# X14-Conversion.net
KiCad netlist of a schematic drawn in EAGLE
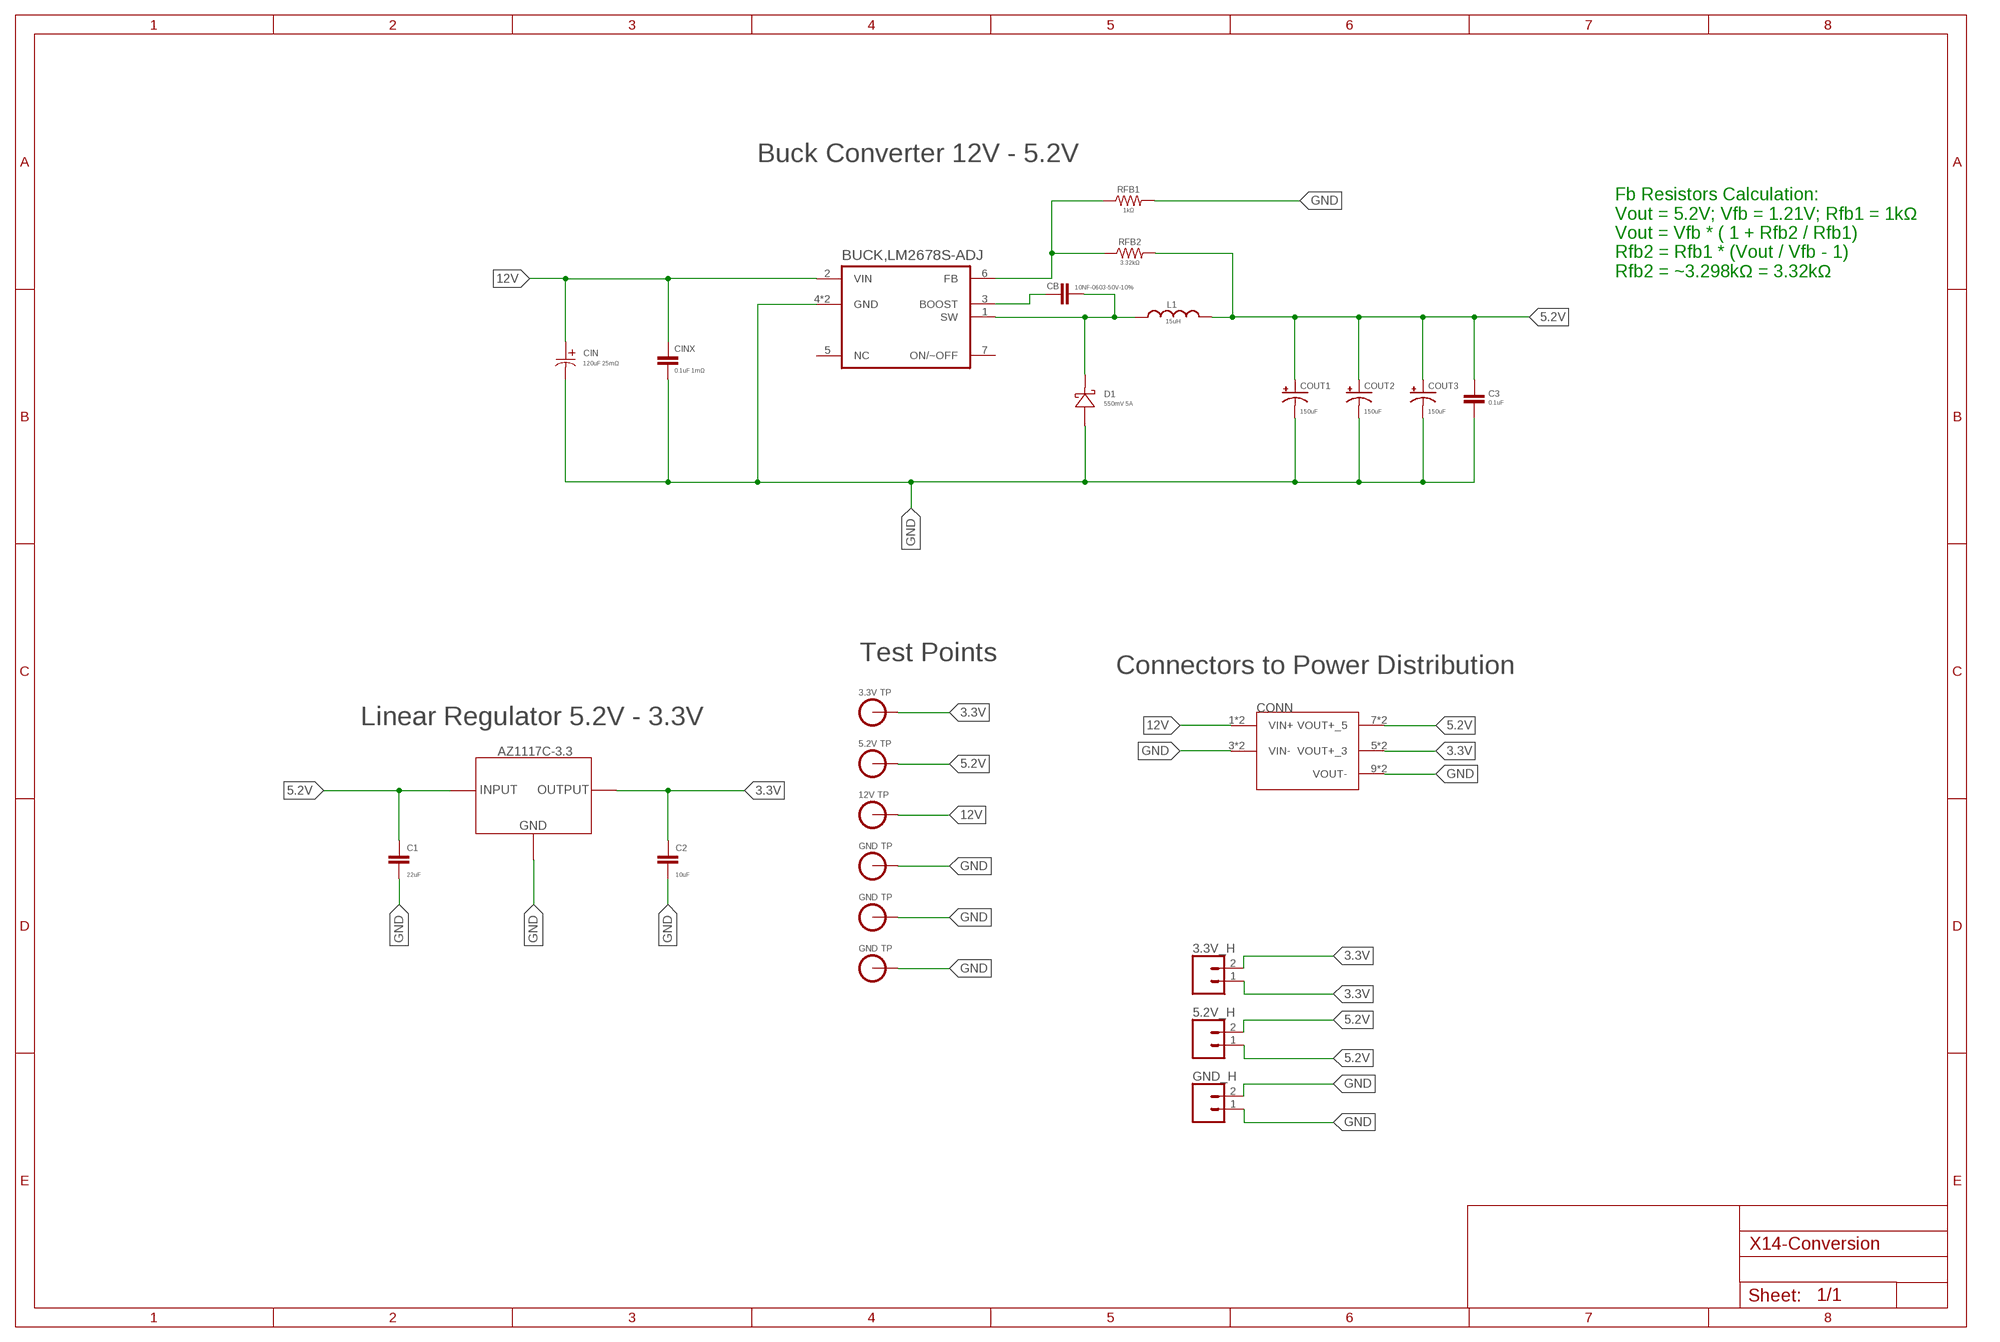
[diagram p0: schematic, sheet 1]

(export (version "E")
  (design (tool "Eeschema 10.0.6"))
  (components
    (comp (ref "3.3V_H")
      (value "CONN_02")
      (footprint "eagle-import:1X02")
      (libsource (lib "eagle-import") (part "CONN_02"))
    )
    (comp (ref "5.2V_H")
      (value "CONN_02")
      (footprint "eagle-import:1X02")
      (libsource (lib "eagle-import") (part "CONN_02"))
    )
    (comp (ref "AZ1117C")
      (value "AZ1117C-3.3")
      (footprint "eagle-import:SOT150P410X160-3N")
      (libsource (lib "eagle-import") (part "SOT150P410X160-3N"))
    )
    (comp (ref "C1")
      (value "22uF")
      (footprint "eagle-import:0805")
      (libsource (lib "eagle-import") (part "22UF-0805-6.3V-20%"))
    )
    (comp (ref "C2")
      (value "10uF")
      (footprint "eagle-import:0603")
      (libsource (lib "eagle-import") (part "10UF-0603-6.3V-20%"))
    )
    (comp (ref "C3")
      (value "0.1uF")
      (footprint "eagle-import:0603")
      (libsource (lib "eagle-import") (part "0.1UF-0603-25V-(+80/-20%)"))
    )
    (comp (ref "CB")
      (value "10NF-0603-50V-10%")
      (footprint "eagle-import:0603")
      (libsource (lib "eagle-import") (part "10NF-0603-50V-10%"))
    )
    (comp (ref "CIN")
      (value "120uF 25mΩ")
      (footprint "eagle-import:PCAP_SVP_C6_PAN")
      (libsource (lib "eagle-import") (part "20SVPF120M"))
    )
    (comp (ref "CINX")
      (value "0.1uF 1mΩ")
      (footprint "eagle-import:0603")
      (libsource (lib "eagle-import") (part "0.1UF-0603-25V-(+80/-20%)"))
    )
    (comp (ref "CONN")
      (value "CONVERSION-DISTRIBUTION")
      (footprint "eagle-import:TSW-105-05-G-S(C-D)")
      (libsource (lib "eagle-import") (part "CONVERSION-DISTRIBUTION"))
    )
    (comp (ref "COUT1")
      (value "150uF")
      (footprint "eagle-import:2917(7343-31-METRIC)")
      (libsource (lib "eagle-import") (part "C-TANTALUM(10UF_150UF)"))
    )
    (comp (ref "COUT2")
      (value "150uF")
      (footprint "eagle-import:2917(7343-31-METRIC)")
      (libsource (lib "eagle-import") (part "C-TANTALUM(10UF_150UF)"))
    )
    (comp (ref "COUT3")
      (value "150uF")
      (footprint "eagle-import:2917(7343-31-METRIC)")
      (libsource (lib "eagle-import") (part "C-TANTALUM(10UF_150UF)"))
    )
    (comp (ref "D1")
      (value "550mV 5A")
      (footprint "eagle-import:CDBG520-G")
      (libsource (lib "eagle-import") (part "CDBG520-G"))
    )
    (comp (ref "GND_H")
      (value "CONN_02")
      (footprint "eagle-import:1X02")
      (libsource (lib "eagle-import") (part "CONN_02"))
    )
    (comp (ref "L1")
      (value "15uH")
      (footprint "eagle-import:HCMA1305")
      (libsource (lib "eagle-import") (part "HCMA1305"))
    )
    (comp (ref "RFB1")
      (value "1kΩ")
      (footprint "eagle-import:0603")
      (libsource (lib "eagle-import") (part "1KOHM-0603-1/10W-1%"))
    )
    (comp (ref "RFB2")
      (value "3.32kΩ")
      (footprint "eagle-import:0603")
      (libsource (lib "eagle-import") (part "3.3KOHM-0603-1/10W-1%"))
    )
    (comp (ref "U$2")
      (value "3.3V_TESTPOINT")
      (footprint "eagle-import:3.3V_TESTPOINT")
      (libsource (lib "eagle-import") (part "3.3V_TESTPOINT"))
    )
    (comp (ref "U$3")
      (value "5.2V_TESTPOINT")
      (footprint "eagle-import:5.2V_TESTPOINT")
      (libsource (lib "eagle-import") (part "5.2V_TESTPOINT"))
    )
    (comp (ref "U$4")
      (value "12V_TESTPOINT")
      (footprint "eagle-import:12V_TESTPOINT")
      (libsource (lib "eagle-import") (part "12V_TESTPOINT"))
    )
    (comp (ref "U$5")
      (value "GND_TESTPOINT")
      (footprint "eagle-import:GND_TESTPOINT")
      (libsource (lib "eagle-import") (part "GND_TESTPOINT"))
    )
    (comp (ref "U$6")
      (value "GND_TESTPOINT")
      (footprint "eagle-import:GND_TESTPOINT")
      (libsource (lib "eagle-import") (part "GND_TESTPOINT"))
    )
    (comp (ref "U$7")
      (value "GND_TESTPOINT")
      (footprint "eagle-import:GND_TESTPOINT")
      (libsource (lib "eagle-import") (part "GND_TESTPOINT"))
    )
    (comp (ref "U1")
      (value "BUCK,LM2678S-ADJ")
      (footprint "eagle-import:TO127P1435X464-8N")
      (fields
        (field (name "DIGI-KEY_PART_NUMBER") "2156-LM2678S-ADJ/NOPB-TI-ND")
        (field (name "MF") "Texas Instruments")
        (field (name "MP") "LM2678S-ADJ")
      )
      (libsource (lib "eagle-import") (part "BUCK,LM2678S-ADJ"))
    )
  )
  (nets
    (net (code "1") (name "3.3V") (class "Default")
      (node (ref "3.3V_H") (pin "1") (pinfunction "1_1") (pintype "passive"))
      (node (ref "3.3V_H") (pin "2") (pinfunction "2_2") (pintype "passive"))
      (node (ref "AZ1117C") (pin "2") (pinfunction "OUTPUT_2") (pintype "bidirectional"))
      (node (ref "AZ1117C") (pin "4") (pinfunction "OUTPUT_4") (pintype "bidirectional"))
      (node (ref "C2") (pin "1") (pinfunction "1_1") (pintype "passive"))
      (node (ref "CONN") (pin "5") (pinfunction "VOUT+_3_5") (pintype "bidirectional"))
      (node (ref "CONN") (pin "6") (pinfunction "VOUT+_3_6") (pintype "bidirectional"))
      (node (ref "U$2") (pin "3.3V") (pinfunction "3.3V_3.3V") (pintype "bidirectional"))
    )
    (net (code "2") (name "5.2V") (class "Default")
      (node (ref "5.2V_H") (pin "1") (pinfunction "1_1") (pintype "passive"))
      (node (ref "5.2V_H") (pin "2") (pinfunction "2_2") (pintype "passive"))
      (node (ref "AZ1117C") (pin "3") (pinfunction "INPUT_3") (pintype "bidirectional"))
      (node (ref "C1") (pin "1") (pinfunction "1_1") (pintype "passive"))
      (node (ref "C3") (pin "1") (pinfunction "1_1") (pintype "passive"))
      (node (ref "CONN") (pin "7") (pinfunction "VOUT+_5_7") (pintype "bidirectional"))
      (node (ref "CONN") (pin "8") (pinfunction "VOUT+_5_8") (pintype "bidirectional"))
      (node (ref "COUT1") (pin "+") (pinfunction "+_+") (pintype "passive"))
      (node (ref "COUT2") (pin "+") (pinfunction "+_+") (pintype "passive"))
      (node (ref "COUT3") (pin "+") (pinfunction "+_+") (pintype "passive"))
      (node (ref "L1") (pin "2") (pinfunction "2_2") (pintype "passive"))
      (node (ref "RFB2") (pin "2") (pinfunction "2_2") (pintype "passive"))
      (node (ref "U$3") (pin "5.2V") (pinfunction "5.2V_5.2V") (pintype "bidirectional"))
    )
    (net (code "3") (name "12V") (class "Default")
      (node (ref "CIN") (pin "1") (pinfunction "1_1") (pintype "passive"))
      (node (ref "CINX") (pin "1") (pinfunction "1_1") (pintype "passive"))
      (node (ref "CONN") (pin "1") (pinfunction "VIN+_1") (pintype "bidirectional"))
      (node (ref "CONN") (pin "2") (pinfunction "VIN+_2") (pintype "bidirectional"))
      (node (ref "U$4") (pin "12V") (pinfunction "12V_12V") (pintype "bidirectional"))
      (node (ref "U1") (pin "2") (pinfunction "VIN_2") (pintype "input"))
    )
    (net (code "4") (name "GND") (class "Default")
      (node (ref "AZ1117C") (pin "1") (pinfunction "GND_1") (pintype "bidirectional"))
      (node (ref "C1") (pin "2") (pinfunction "2_2") (pintype "passive"))
      (node (ref "C2") (pin "2") (pinfunction "2_2") (pintype "passive"))
      (node (ref "C3") (pin "2") (pinfunction "2_2") (pintype "passive"))
      (node (ref "CIN") (pin "2") (pinfunction "2_2") (pintype "passive"))
      (node (ref "CINX") (pin "2") (pinfunction "2_2") (pintype "passive"))
      (node (ref "CONN") (pin "10") (pinfunction "VOUT-_10") (pintype "bidirectional"))
      (node (ref "CONN") (pin "3") (pinfunction "VIN-_3") (pintype "bidirectional"))
      (node (ref "CONN") (pin "4") (pinfunction "VIN-_4") (pintype "bidirectional"))
      (node (ref "CONN") (pin "9") (pinfunction "VOUT-_9") (pintype "bidirectional"))
      (node (ref "COUT1") (pin "-") (pinfunction "-_-") (pintype "passive"))
      (node (ref "COUT2") (pin "-") (pinfunction "-_-") (pintype "passive"))
      (node (ref "COUT3") (pin "-") (pinfunction "-_-") (pintype "passive"))
      (node (ref "D1") (pin "2") (pinfunction "2_2") (pintype "passive"))
      (node (ref "GND_H") (pin "1") (pinfunction "1_1") (pintype "passive"))
      (node (ref "GND_H") (pin "2") (pinfunction "2_2") (pintype "passive"))
      (node (ref "RFB1") (pin "2") (pinfunction "2_2") (pintype "passive"))
      (node (ref "U$5") (pin "GND") (pinfunction "GND_GND") (pintype "bidirectional"))
      (node (ref "U$6") (pin "GND") (pinfunction "GND_GND") (pintype "bidirectional"))
      (node (ref "U$7") (pin "GND") (pinfunction "GND_GND") (pintype "bidirectional"))
      (node (ref "U1") (pin "4") (pinfunction "GND_4") (pintype "power_in"))
      (node (ref "U1") (pin "8") (pinfunction "GND_8") (pintype "power_in"))
    )
    (net (code "5") (name "Net-(U1-BOOST)") (class "Default")
      (node (ref "CB") (pin "1") (pinfunction "1_1") (pintype "passive"))
      (node (ref "U1") (pin "3") (pinfunction "BOOST_3") (pintype "input"))
    )
    (net (code "6") (name "Net-(U1-FB)") (class "Default")
      (node (ref "RFB1") (pin "1") (pinfunction "1_1") (pintype "passive"))
      (node (ref "RFB2") (pin "1") (pinfunction "1_1") (pintype "passive"))
      (node (ref "U1") (pin "6") (pinfunction "FB_6") (pintype "input"))
    )
    (net (code "7") (name "Net-(U1-SW)") (class "Default")
      (node (ref "CB") (pin "2") (pinfunction "2_2") (pintype "passive"))
      (node (ref "D1") (pin "1") (pinfunction "1_1") (pintype "passive"))
      (node (ref "L1") (pin "1") (pinfunction "1_1") (pintype "passive"))
      (node (ref "U1") (pin "1") (pinfunction "SW_1") (pintype "output"))
    )
    (net (code "8") (name "unconnected-(U1-NC-Pad5)") (class "Default")
      (node (ref "U1") (pin "5") (pinfunction "NC_5") (pintype "bidirectional"))
    )
    (net (code "9") (name "unconnected-(U1-ON{slash}~{OFF}-Pad7)") (class "Default")
      (node (ref "U1") (pin "7") (pinfunction "ON/~{OFF}_7") (pintype "input"))
    )
  )
)
